# BMS_Bottom_Segment.net
KiCad netlist of a schematic drawn in EAGLE
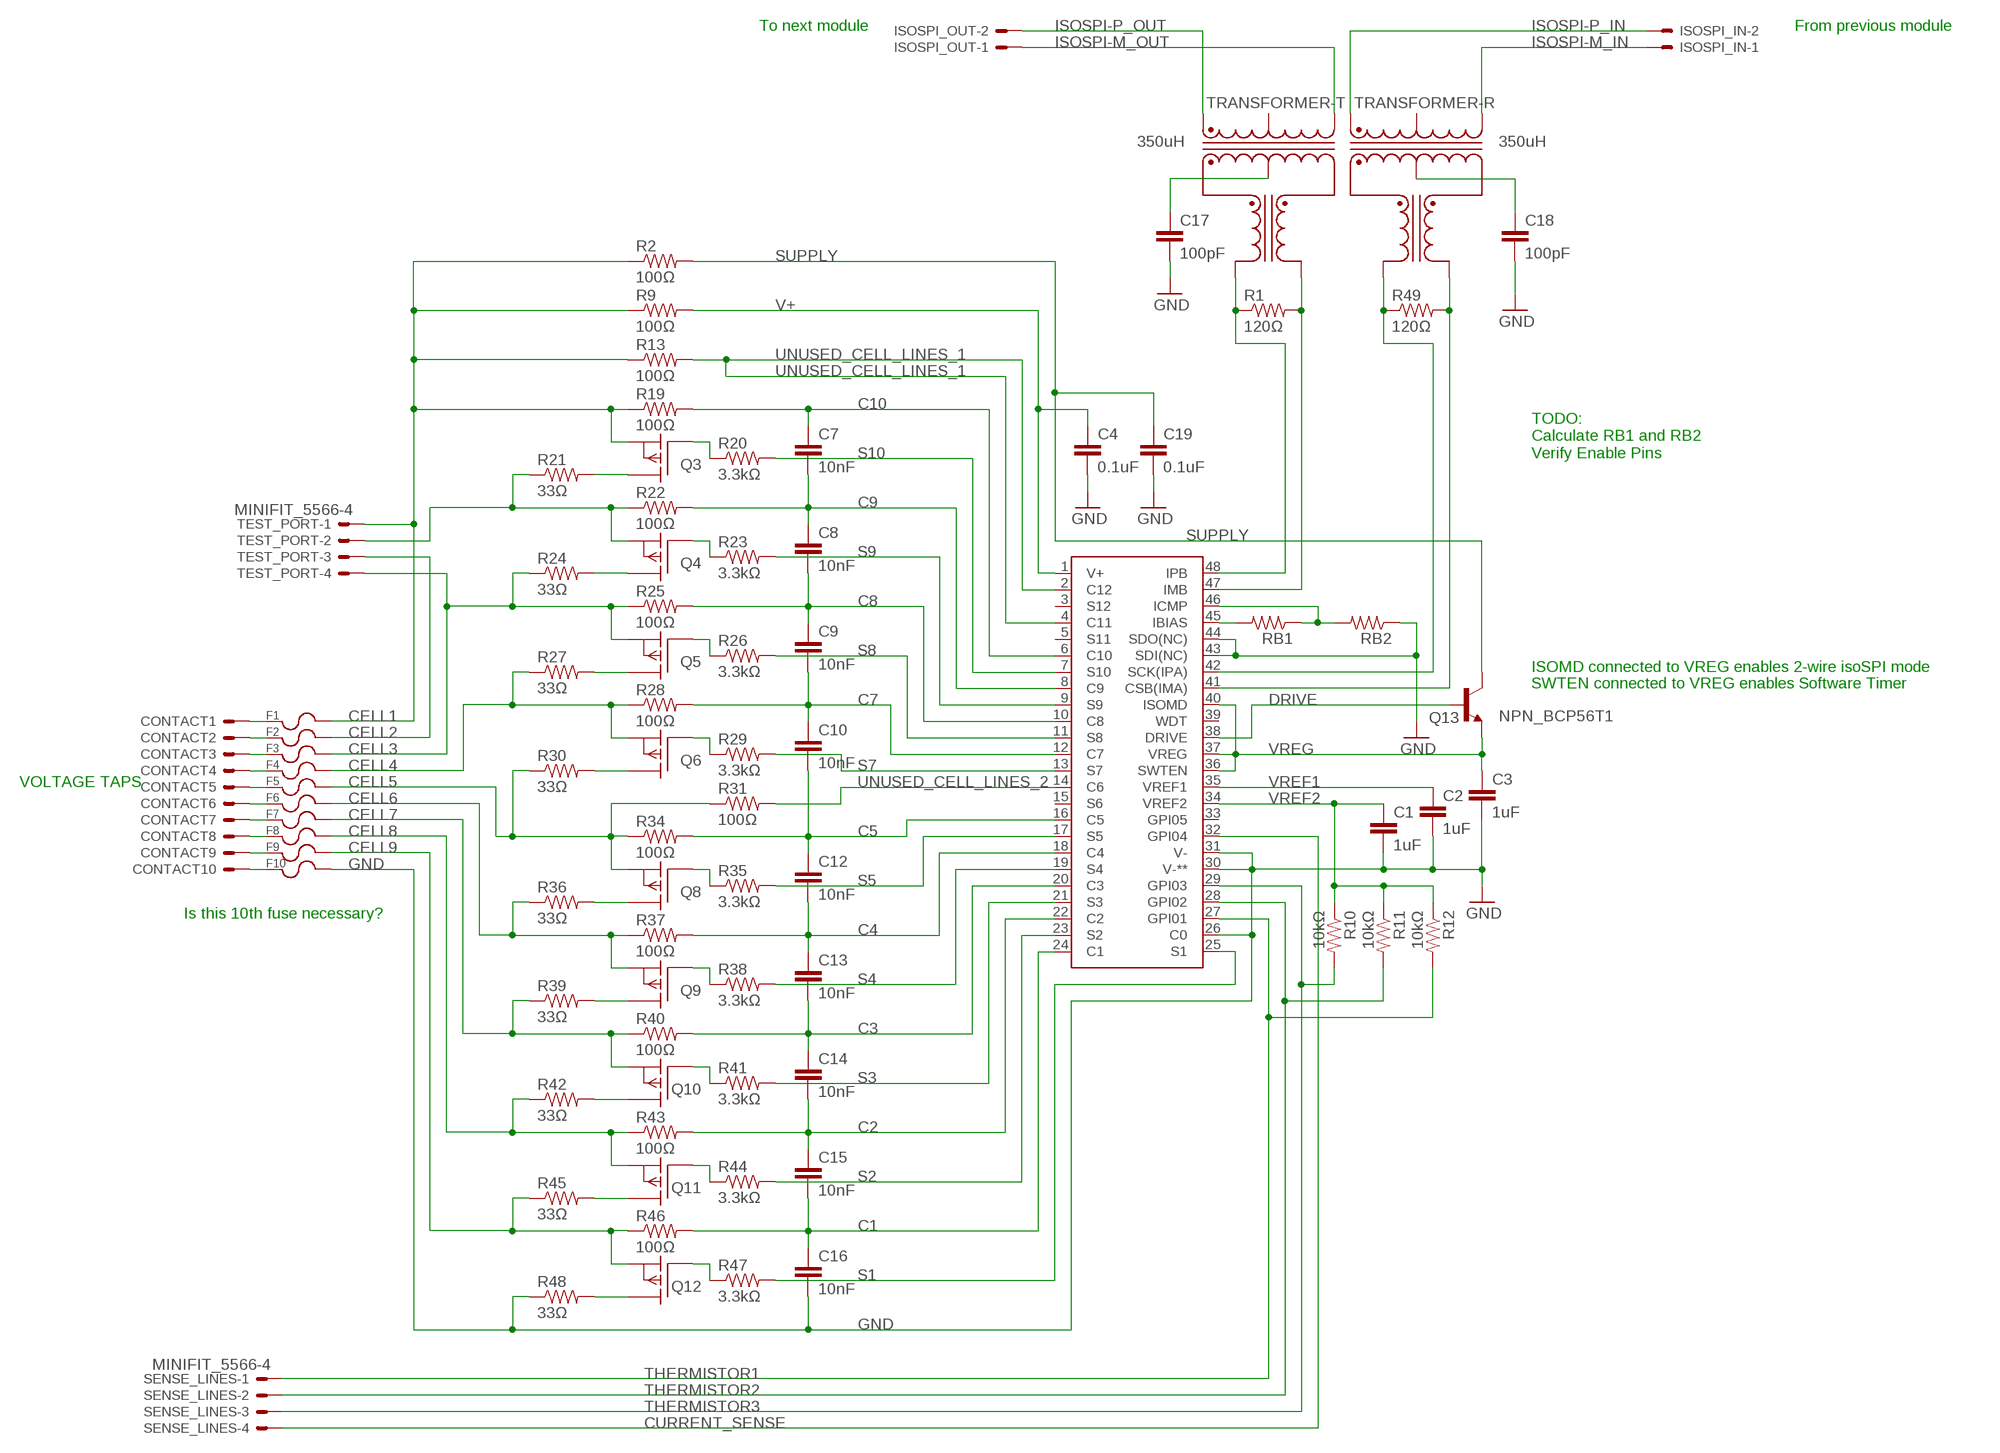
[diagram p0: schematic, sheet 1]

(export (version "E")
  (design (tool "Eeschema 10.0.6"))
  (components
    (comp (ref "C1")
      (value "1uF")
      (footprint "eagle-import:0805")
      (libsource (lib "eagle-import") (part "CAP0805"))
    )
    (comp (ref "C2")
      (value "1uF")
      (footprint "eagle-import:0805")
      (libsource (lib "eagle-import") (part "CAP0805"))
    )
    (comp (ref "C3")
      (value "1uF")
      (footprint "eagle-import:0805")
      (libsource (lib "eagle-import") (part "CAP0805"))
    )
    (comp (ref "C4")
      (value "0.1uF")
      (footprint "eagle-import:0805")
      (libsource (lib "eagle-import") (part "CAP0805"))
    )
    (comp (ref "C7")
      (value "10nF")
      (footprint "eagle-import:0805")
      (libsource (lib "eagle-import") (part "CAP0805"))
    )
    (comp (ref "C8")
      (value "10nF")
      (footprint "eagle-import:0805")
      (libsource (lib "eagle-import") (part "CAP0805"))
    )
    (comp (ref "C9")
      (value "10nF")
      (footprint "eagle-import:0805")
      (libsource (lib "eagle-import") (part "CAP0805"))
    )
    (comp (ref "C10")
      (value "10nF")
      (footprint "eagle-import:0805")
      (libsource (lib "eagle-import") (part "CAP0805"))
    )
    (comp (ref "C12")
      (value "10nF")
      (footprint "eagle-import:0805")
      (libsource (lib "eagle-import") (part "CAP0805"))
    )
    (comp (ref "C13")
      (value "10nF")
      (footprint "eagle-import:0805")
      (libsource (lib "eagle-import") (part "CAP0805"))
    )
    (comp (ref "C14")
      (value "10nF")
      (footprint "eagle-import:0805")
      (libsource (lib "eagle-import") (part "CAP0805"))
    )
    (comp (ref "C15")
      (value "10nF")
      (footprint "eagle-import:0805")
      (libsource (lib "eagle-import") (part "CAP0805"))
    )
    (comp (ref "C16")
      (value "10nF")
      (footprint "eagle-import:0805")
      (libsource (lib "eagle-import") (part "CAP0805"))
    )
    (comp (ref "C17")
      (value "100pF")
      (footprint "eagle-import:0805")
      (libsource (lib "eagle-import") (part "CAP0805"))
    )
    (comp (ref "C18")
      (value "100pF")
      (footprint "eagle-import:0805")
      (libsource (lib "eagle-import") (part "CAP0805"))
    )
    (comp (ref "C19")
      (value "0.1uF")
      (footprint "eagle-import:0805")
      (libsource (lib "eagle-import") (part "CAP0805"))
    )
    (comp (ref "CONTACT1")
      (value "SPRING_CONTACT")
      (footprint "eagle-import:S1791-42R")
      (libsource (lib "eagle-import") (part "SPRING_CONTACT"))
    )
    (comp (ref "CONTACT2")
      (value "SPRING_CONTACT")
      (footprint "eagle-import:S1791-42R")
      (libsource (lib "eagle-import") (part "SPRING_CONTACT"))
    )
    (comp (ref "CONTACT3")
      (value "SPRING_CONTACT")
      (footprint "eagle-import:S1791-42R")
      (libsource (lib "eagle-import") (part "SPRING_CONTACT"))
    )
    (comp (ref "CONTACT4")
      (value "SPRING_CONTACT")
      (footprint "eagle-import:S1791-42R")
      (libsource (lib "eagle-import") (part "SPRING_CONTACT"))
    )
    (comp (ref "CONTACT5")
      (value "SPRING_CONTACT")
      (footprint "eagle-import:S1791-42R")
      (libsource (lib "eagle-import") (part "SPRING_CONTACT"))
    )
    (comp (ref "CONTACT6")
      (value "SPRING_CONTACT")
      (footprint "eagle-import:S1791-42R")
      (libsource (lib "eagle-import") (part "SPRING_CONTACT"))
    )
    (comp (ref "CONTACT7")
      (value "SPRING_CONTACT")
      (footprint "eagle-import:S1791-42R")
      (libsource (lib "eagle-import") (part "SPRING_CONTACT"))
    )
    (comp (ref "CONTACT8")
      (value "SPRING_CONTACT")
      (footprint "eagle-import:S1791-42R")
      (libsource (lib "eagle-import") (part "SPRING_CONTACT"))
    )
    (comp (ref "CONTACT9")
      (value "SPRING_CONTACT")
      (footprint "eagle-import:S1791-42R")
      (libsource (lib "eagle-import") (part "SPRING_CONTACT"))
    )
    (comp (ref "CONTACT10")
      (value "SPRING_CONTACT")
      (footprint "eagle-import:S1791-42R")
      (libsource (lib "eagle-import") (part "SPRING_CONTACT"))
    )
    (comp (ref "F1")
      (value "0751.0110_FUSE_CLIP")
      (footprint "eagle-import:0751.0110")
      (libsource (lib "eagle-import") (part "0751.0110_FUSE_CLIP"))
    )
    (comp (ref "F2")
      (value "0751.0110_FUSE_CLIP")
      (footprint "eagle-import:0751.0110")
      (libsource (lib "eagle-import") (part "0751.0110_FUSE_CLIP"))
    )
    (comp (ref "F3")
      (value "0751.0110_FUSE_CLIP")
      (footprint "eagle-import:0751.0110")
      (libsource (lib "eagle-import") (part "0751.0110_FUSE_CLIP"))
    )
    (comp (ref "F4")
      (value "0751.0110_FUSE_CLIP")
      (footprint "eagle-import:0751.0110")
      (libsource (lib "eagle-import") (part "0751.0110_FUSE_CLIP"))
    )
    (comp (ref "F5")
      (value "0751.0110_FUSE_CLIP")
      (footprint "eagle-import:0751.0110")
      (libsource (lib "eagle-import") (part "0751.0110_FUSE_CLIP"))
    )
    (comp (ref "F6")
      (value "0751.0110_FUSE_CLIP")
      (footprint "eagle-import:0751.0110")
      (libsource (lib "eagle-import") (part "0751.0110_FUSE_CLIP"))
    )
    (comp (ref "F7")
      (value "0751.0110_FUSE_CLIP")
      (footprint "eagle-import:0751.0110")
      (libsource (lib "eagle-import") (part "0751.0110_FUSE_CLIP"))
    )
    (comp (ref "F8")
      (value "0751.0110_FUSE_CLIP")
      (footprint "eagle-import:0751.0110")
      (libsource (lib "eagle-import") (part "0751.0110_FUSE_CLIP"))
    )
    (comp (ref "F9")
      (value "0751.0110_FUSE_CLIP")
      (footprint "eagle-import:0751.0110")
      (libsource (lib "eagle-import") (part "0751.0110_FUSE_CLIP"))
    )
    (comp (ref "F10")
      (value "0751.0110_FUSE_CLIP")
      (footprint "eagle-import:0751.0110")
      (libsource (lib "eagle-import") (part "0751.0110_FUSE_CLIP"))
    )
    (comp (ref "ISOSPI_IN")
      (value "MINIFIT_5566-2")
      (footprint "eagle-import:MINIFIT_5566-2")
      (libsource (lib "eagle-import") (part "MINIFIT_5566-2"))
    )
    (comp (ref "ISOSPI_OUT")
      (value "MINIFIT_5566-2")
      (footprint "eagle-import:MINIFIT_5566-2")
      (libsource (lib "eagle-import") (part "MINIFIT_5566-2"))
    )
    (comp (ref "Q3")
      (value "P-CHANNEL_MOSFET_DMP3099L-7")
      (footprint "eagle-import:SOT23")
      (libsource (lib "eagle-import") (part "P-CHANNEL_MOSFET_DMP3099L-7"))
    )
    (comp (ref "Q4")
      (value "P-CHANNEL_MOSFET_DMP3099L-7")
      (footprint "eagle-import:SOT23")
      (libsource (lib "eagle-import") (part "P-CHANNEL_MOSFET_DMP3099L-7"))
    )
    (comp (ref "Q5")
      (value "P-CHANNEL_MOSFET_DMP3099L-7")
      (footprint "eagle-import:SOT23")
      (libsource (lib "eagle-import") (part "P-CHANNEL_MOSFET_DMP3099L-7"))
    )
    (comp (ref "Q6")
      (value "P-CHANNEL_MOSFET_DMP3099L-7")
      (footprint "eagle-import:SOT23")
      (libsource (lib "eagle-import") (part "P-CHANNEL_MOSFET_DMP3099L-7"))
    )
    (comp (ref "Q8")
      (value "P-CHANNEL_MOSFET_DMP3099L-7")
      (footprint "eagle-import:SOT23")
      (libsource (lib "eagle-import") (part "P-CHANNEL_MOSFET_DMP3099L-7"))
    )
    (comp (ref "Q9")
      (value "P-CHANNEL_MOSFET_DMP3099L-7")
      (footprint "eagle-import:SOT23")
      (libsource (lib "eagle-import") (part "P-CHANNEL_MOSFET_DMP3099L-7"))
    )
    (comp (ref "Q10")
      (value "P-CHANNEL_MOSFET_DMP3099L-7")
      (footprint "eagle-import:SOT23")
      (libsource (lib "eagle-import") (part "P-CHANNEL_MOSFET_DMP3099L-7"))
    )
    (comp (ref "Q11")
      (value "P-CHANNEL_MOSFET_DMP3099L-7")
      (footprint "eagle-import:SOT23")
      (libsource (lib "eagle-import") (part "P-CHANNEL_MOSFET_DMP3099L-7"))
    )
    (comp (ref "Q12")
      (value "P-CHANNEL_MOSFET_DMP3099L-7")
      (footprint "eagle-import:SOT23")
      (libsource (lib "eagle-import") (part "P-CHANNEL_MOSFET_DMP3099L-7"))
    )
    (comp (ref "Q13")
      (value "NPN_BCP56T1")
      (footprint "eagle-import:SOT223")
      (libsource (lib "eagle-import") (part "NPN_BCP56T1"))
    )
    (comp (ref "R1")
      (value "120Ω")
      (footprint "eagle-import:0805")
      (libsource (lib "eagle-import") (part "RESISTOR0805-RES"))
    )
    (comp (ref "R2")
      (value "100Ω")
      (footprint "eagle-import:0805")
      (libsource (lib "eagle-import") (part "RESISTOR0805-RES"))
    )
    (comp (ref "R9")
      (value "100Ω")
      (footprint "eagle-import:0805")
      (libsource (lib "eagle-import") (part "RESISTOR0805-RES"))
    )
    (comp (ref "R10")
      (value "10kΩ")
      (footprint "eagle-import:0805")
      (libsource (lib "eagle-import") (part "RESISTOR0805-RES"))
    )
    (comp (ref "R11")
      (value "10kΩ")
      (footprint "eagle-import:0805")
      (libsource (lib "eagle-import") (part "RESISTOR0805-RES"))
    )
    (comp (ref "R12")
      (value "10kΩ")
      (footprint "eagle-import:0805")
      (libsource (lib "eagle-import") (part "RESISTOR0805-RES"))
    )
    (comp (ref "R13")
      (value "100Ω")
      (footprint "eagle-import:0805")
      (libsource (lib "eagle-import") (part "RESISTOR0805-RES"))
    )
    (comp (ref "R19")
      (value "100Ω")
      (footprint "eagle-import:0805")
      (libsource (lib "eagle-import") (part "RESISTOR0805-RES"))
    )
    (comp (ref "R20")
      (value "3.3kΩ")
      (footprint "eagle-import:0805")
      (libsource (lib "eagle-import") (part "RESISTOR0805-RES"))
    )
    (comp (ref "R21")
      (value "33Ω")
      (footprint "eagle-import:R2512")
      (libsource (lib "eagle-import") (part "RESISTOR2512"))
    )
    (comp (ref "R22")
      (value "100Ω")
      (footprint "eagle-import:0805")
      (libsource (lib "eagle-import") (part "RESISTOR0805-RES"))
    )
    (comp (ref "R23")
      (value "3.3kΩ")
      (footprint "eagle-import:0805")
      (libsource (lib "eagle-import") (part "RESISTOR0805-RES"))
    )
    (comp (ref "R24")
      (value "33Ω")
      (footprint "eagle-import:R2512")
      (libsource (lib "eagle-import") (part "RESISTOR2512"))
    )
    (comp (ref "R25")
      (value "100Ω")
      (footprint "eagle-import:0805")
      (libsource (lib "eagle-import") (part "RESISTOR0805-RES"))
    )
    (comp (ref "R26")
      (value "3.3kΩ")
      (footprint "eagle-import:0805")
      (libsource (lib "eagle-import") (part "RESISTOR0805-RES"))
    )
    (comp (ref "R27")
      (value "33Ω")
      (footprint "eagle-import:R2512")
      (libsource (lib "eagle-import") (part "RESISTOR2512"))
    )
    (comp (ref "R28")
      (value "100Ω")
      (footprint "eagle-import:0805")
      (libsource (lib "eagle-import") (part "RESISTOR0805-RES"))
    )
    (comp (ref "R29")
      (value "3.3kΩ")
      (footprint "eagle-import:0805")
      (libsource (lib "eagle-import") (part "RESISTOR0805-RES"))
    )
    (comp (ref "R30")
      (value "33Ω")
      (footprint "eagle-import:R2512")
      (libsource (lib "eagle-import") (part "RESISTOR2512"))
    )
    (comp (ref "R31")
      (value "100Ω")
      (footprint "eagle-import:0805")
      (libsource (lib "eagle-import") (part "RESISTOR0805-RES"))
    )
    (comp (ref "R34")
      (value "100Ω")
      (footprint "eagle-import:0805")
      (libsource (lib "eagle-import") (part "RESISTOR0805-RES"))
    )
    (comp (ref "R35")
      (value "3.3kΩ")
      (footprint "eagle-import:0805")
      (libsource (lib "eagle-import") (part "RESISTOR0805-RES"))
    )
    (comp (ref "R36")
      (value "33Ω")
      (footprint "eagle-import:R2512")
      (libsource (lib "eagle-import") (part "RESISTOR2512"))
    )
    (comp (ref "R37")
      (value "100Ω")
      (footprint "eagle-import:0805")
      (libsource (lib "eagle-import") (part "RESISTOR0805-RES"))
    )
    (comp (ref "R38")
      (value "3.3kΩ")
      (footprint "eagle-import:0805")
      (libsource (lib "eagle-import") (part "RESISTOR0805-RES"))
    )
    (comp (ref "R39")
      (value "33Ω")
      (footprint "eagle-import:R2512")
      (libsource (lib "eagle-import") (part "RESISTOR2512"))
    )
    (comp (ref "R40")
      (value "100Ω")
      (footprint "eagle-import:0805")
      (libsource (lib "eagle-import") (part "RESISTOR0805-RES"))
    )
    (comp (ref "R41")
      (value "3.3kΩ")
      (footprint "eagle-import:0805")
      (libsource (lib "eagle-import") (part "RESISTOR0805-RES"))
    )
    (comp (ref "R42")
      (value "33Ω")
      (footprint "eagle-import:R2512")
      (libsource (lib "eagle-import") (part "RESISTOR2512"))
    )
    (comp (ref "R43")
      (value "100Ω")
      (footprint "eagle-import:0805")
      (libsource (lib "eagle-import") (part "RESISTOR0805-RES"))
    )
    (comp (ref "R44")
      (value "3.3kΩ")
      (footprint "eagle-import:0805")
      (libsource (lib "eagle-import") (part "RESISTOR0805-RES"))
    )
    (comp (ref "R45")
      (value "33Ω")
      (footprint "eagle-import:R2512")
      (libsource (lib "eagle-import") (part "RESISTOR2512"))
    )
    (comp (ref "R46")
      (value "100Ω")
      (footprint "eagle-import:0805")
      (libsource (lib "eagle-import") (part "RESISTOR0805-RES"))
    )
    (comp (ref "R47")
      (value "3.3kΩ")
      (footprint "eagle-import:0805")
      (libsource (lib "eagle-import") (part "RESISTOR0805-RES"))
    )
    (comp (ref "R48")
      (value "33Ω")
      (footprint "eagle-import:R2512")
      (libsource (lib "eagle-import") (part "RESISTOR2512"))
    )
    (comp (ref "R49")
      (value "120Ω")
      (footprint "eagle-import:0805")
      (libsource (lib "eagle-import") (part "RESISTOR0805-RES"))
    )
    (comp (ref "RB1")
      (value "RESISTOR0805-RES")
      (footprint "eagle-import:0805")
      (libsource (lib "eagle-import") (part "RESISTOR0805-RES"))
    )
    (comp (ref "RB2")
      (value "RESISTOR0805-RES")
      (footprint "eagle-import:0805")
      (libsource (lib "eagle-import") (part "RESISTOR0805-RES"))
    )
    (comp (ref "SENSE_LINES")
      (value "MINIFIT_5566-4")
      (footprint "eagle-import:MINIFIT_5566-4")
      (libsource (lib "eagle-import") (part "MINIFIT_5566-4"))
    )
    (comp (ref "TEST_PORT")
      (value "MINIFIT_5566-4")
      (footprint "eagle-import:MINIFIT_5566-4")
      (libsource (lib "eagle-import") (part "MINIFIT_5566-4"))
    )
    (comp (ref "TRANSFORMER-")
      (value "350uH")
      (footprint "eagle-import:749010013")
      (libsource (lib "eagle-import") (part "TRANSFORMER_749010013"))
    )
    (comp (ref "U$2")
      (value "LTC6804-1")
      (footprint "eagle-import:LTC6804")
      (libsource (lib "eagle-import") (part "LTC6804-1"))
    )
  )
  (nets
    (net (code "1") (name "/C1") (class "Default")
      (node (ref "C15") (pin "2") (pinfunction "2_2") (pintype "passive"))
      (node (ref "C16") (pin "1") (pinfunction "1_1") (pintype "passive"))
      (node (ref "R46") (pin "2") (pinfunction "2_2") (pintype "passive"))
      (node (ref "U$2") (pin "24") (pinfunction "C1_24") (pintype "bidirectional"))
    )
    (net (code "2") (name "/C2") (class "Default")
      (node (ref "C14") (pin "2") (pinfunction "2_2") (pintype "passive"))
      (node (ref "C15") (pin "1") (pinfunction "1_1") (pintype "passive"))
      (node (ref "R43") (pin "2") (pinfunction "2_2") (pintype "passive"))
      (node (ref "U$2") (pin "22") (pinfunction "C2_22") (pintype "bidirectional"))
    )
    (net (code "3") (name "/C3") (class "Default")
      (node (ref "C13") (pin "2") (pinfunction "2_2") (pintype "passive"))
      (node (ref "C14") (pin "1") (pinfunction "1_1") (pintype "passive"))
      (node (ref "R40") (pin "2") (pinfunction "2_2") (pintype "passive"))
      (node (ref "U$2") (pin "20") (pinfunction "C3_20") (pintype "bidirectional"))
    )
    (net (code "4") (name "/C4") (class "Default")
      (node (ref "C12") (pin "2") (pinfunction "2_2") (pintype "passive"))
      (node (ref "C13") (pin "1") (pinfunction "1_1") (pintype "passive"))
      (node (ref "R37") (pin "2") (pinfunction "2_2") (pintype "passive"))
      (node (ref "U$2") (pin "18") (pinfunction "C4_18") (pintype "bidirectional"))
    )
    (net (code "5") (name "/C5") (class "Default")
      (node (ref "C10") (pin "2") (pinfunction "2_2") (pintype "passive"))
      (node (ref "C12") (pin "1") (pinfunction "1_1") (pintype "passive"))
      (node (ref "R34") (pin "2") (pinfunction "2_2") (pintype "passive"))
      (node (ref "U$2") (pin "16") (pinfunction "C5_16") (pintype "bidirectional"))
    )
    (net (code "6") (name "/C7") (class "Default")
      (node (ref "C10") (pin "1") (pinfunction "1_1") (pintype "passive"))
      (node (ref "C9") (pin "2") (pinfunction "2_2") (pintype "passive"))
      (node (ref "R28") (pin "2") (pinfunction "2_2") (pintype "passive"))
      (node (ref "U$2") (pin "12") (pinfunction "C7_12") (pintype "bidirectional"))
    )
    (net (code "7") (name "/C8") (class "Default")
      (node (ref "C8") (pin "2") (pinfunction "2_2") (pintype "passive"))
      (node (ref "C9") (pin "1") (pinfunction "1_1") (pintype "passive"))
      (node (ref "R25") (pin "2") (pinfunction "2_2") (pintype "passive"))
      (node (ref "U$2") (pin "10") (pinfunction "C8_10") (pintype "bidirectional"))
    )
    (net (code "8") (name "/C9") (class "Default")
      (node (ref "C7") (pin "2") (pinfunction "2_2") (pintype "passive"))
      (node (ref "C8") (pin "1") (pinfunction "1_1") (pintype "passive"))
      (node (ref "R22") (pin "2") (pinfunction "2_2") (pintype "passive"))
      (node (ref "U$2") (pin "8") (pinfunction "C9_8") (pintype "bidirectional"))
    )
    (net (code "9") (name "/C10") (class "Default")
      (node (ref "C7") (pin "1") (pinfunction "1_1") (pintype "passive"))
      (node (ref "R19") (pin "2") (pinfunction "2_2") (pintype "passive"))
      (node (ref "U$2") (pin "6") (pinfunction "C10_6") (pintype "bidirectional"))
    )
    (net (code "10") (name "/CELL1") (class "Default")
      (node (ref "F1") (pin "R1") (pinfunction "2_R1") (pintype "bidirectional"))
      (node (ref "F1") (pin "R2") (pinfunction "2_R2") (pintype "bidirectional"))
      (node (ref "Q3") (pin "2") (pinfunction "S_2") (pintype "passive"))
      (node (ref "R13") (pin "1") (pinfunction "1_1") (pintype "passive"))
      (node (ref "R19") (pin "1") (pinfunction "1_1") (pintype "passive"))
      (node (ref "R2") (pin "1") (pinfunction "1_1") (pintype "passive"))
      (node (ref "R9") (pin "1") (pinfunction "1_1") (pintype "passive"))
      (node (ref "TEST_PORT") (pin "1") (pinfunction "S_1") (pintype "passive"))
    )
    (net (code "11") (name "/CELL2") (class "Default")
      (node (ref "F2") (pin "R1") (pinfunction "2_R1") (pintype "bidirectional"))
      (node (ref "F2") (pin "R2") (pinfunction "2_R2") (pintype "bidirectional"))
      (node (ref "Q4") (pin "2") (pinfunction "S_2") (pintype "passive"))
      (node (ref "R21") (pin "1") (pinfunction "1_1") (pintype "passive"))
      (node (ref "R22") (pin "1") (pinfunction "1_1") (pintype "passive"))
      (node (ref "TEST_PORT") (pin "2") (pinfunction "S_2") (pintype "passive"))
      (node (ref "TEST_PORT") (pin "3") (pinfunction "S_3") (pintype "passive"))
    )
    (net (code "12") (name "/CELL3") (class "Default")
      (node (ref "F3") (pin "R1") (pinfunction "2_R1") (pintype "bidirectional"))
      (node (ref "F3") (pin "R2") (pinfunction "2_R2") (pintype "bidirectional"))
      (node (ref "Q5") (pin "2") (pinfunction "S_2") (pintype "passive"))
      (node (ref "R24") (pin "1") (pinfunction "1_1") (pintype "passive"))
      (node (ref "R25") (pin "1") (pinfunction "1_1") (pintype "passive"))
      (node (ref "TEST_PORT") (pin "4") (pinfunction "S_4") (pintype "passive"))
    )
    (net (code "13") (name "/CELL4") (class "Default")
      (node (ref "F4") (pin "R1") (pinfunction "2_R1") (pintype "bidirectional"))
      (node (ref "F4") (pin "R2") (pinfunction "2_R2") (pintype "bidirectional"))
      (node (ref "Q6") (pin "2") (pinfunction "S_2") (pintype "passive"))
      (node (ref "R27") (pin "1") (pinfunction "1_1") (pintype "passive"))
      (node (ref "R28") (pin "1") (pinfunction "1_1") (pintype "passive"))
    )
    (net (code "14") (name "/CELL5") (class "Default")
      (node (ref "F5") (pin "R1") (pinfunction "2_R1") (pintype "bidirectional"))
      (node (ref "F5") (pin "R2") (pinfunction "2_R2") (pintype "bidirectional"))
      (node (ref "Q8") (pin "2") (pinfunction "S_2") (pintype "passive"))
      (node (ref "R30") (pin "1") (pinfunction "1_1") (pintype "passive"))
      (node (ref "R31") (pin "1") (pinfunction "1_1") (pintype "passive"))
      (node (ref "R34") (pin "1") (pinfunction "1_1") (pintype "passive"))
    )
    (net (code "15") (name "/CELL6") (class "Default")
      (node (ref "F6") (pin "R1") (pinfunction "2_R1") (pintype "bidirectional"))
      (node (ref "F6") (pin "R2") (pinfunction "2_R2") (pintype "bidirectional"))
      (node (ref "Q9") (pin "2") (pinfunction "S_2") (pintype "passive"))
      (node (ref "R36") (pin "1") (pinfunction "1_1") (pintype "passive"))
      (node (ref "R37") (pin "1") (pinfunction "1_1") (pintype "passive"))
    )
    (net (code "16") (name "/CELL7") (class "Default")
      (node (ref "F7") (pin "R1") (pinfunction "2_R1") (pintype "bidirectional"))
      (node (ref "F7") (pin "R2") (pinfunction "2_R2") (pintype "bidirectional"))
      (node (ref "Q10") (pin "2") (pinfunction "S_2") (pintype "passive"))
      (node (ref "R39") (pin "1") (pinfunction "1_1") (pintype "passive"))
      (node (ref "R40") (pin "1") (pinfunction "1_1") (pintype "passive"))
    )
    (net (code "17") (name "/CELL8") (class "Default")
      (node (ref "F8") (pin "R1") (pinfunction "2_R1") (pintype "bidirectional"))
      (node (ref "F8") (pin "R2") (pinfunction "2_R2") (pintype "bidirectional"))
      (node (ref "Q11") (pin "2") (pinfunction "S_2") (pintype "passive"))
      (node (ref "R42") (pin "1") (pinfunction "1_1") (pintype "passive"))
      (node (ref "R43") (pin "1") (pinfunction "1_1") (pintype "passive"))
    )
    (net (code "18") (name "/CELL9") (class "Default")
      (node (ref "F9") (pin "R1") (pinfunction "2_R1") (pintype "bidirectional"))
      (node (ref "F9") (pin "R2") (pinfunction "2_R2") (pintype "bidirectional"))
      (node (ref "Q12") (pin "2") (pinfunction "S_2") (pintype "passive"))
      (node (ref "R45") (pin "1") (pinfunction "1_1") (pintype "passive"))
      (node (ref "R46") (pin "1") (pinfunction "1_1") (pintype "passive"))
    )
    (net (code "19") (name "/CURRENT_SENSE") (class "Default")
      (node (ref "SENSE_LINES") (pin "4") (pinfunction "S_4") (pintype "passive"))
      (node (ref "U$2") (pin "32") (pinfunction "GPI04_32") (pintype "bidirectional"))
    )
    (net (code "20") (name "/DRIVE") (class "Default")
      (node (ref "Q13") (pin "1") (pinfunction "BASE_1") (pintype "passive"))
      (node (ref "U$2") (pin "38") (pinfunction "DRIVE_38") (pintype "bidirectional"))
    )
    (net (code "21") (name "/ISOSPI-M_IN") (class "Default")
      (node (ref "ISOSPI_IN") (pin "1") (pinfunction "S_1") (pintype "passive"))
      (node (ref "TRANSFORMER-") (pin "8") (pinfunction "D-_8") (pintype "passive"))
    )
    (net (code "22") (name "/ISOSPI-M_OUT") (class "Default")
      (node (ref "ISOSPI_OUT") (pin "1") (pinfunction "S_1") (pintype "passive"))
      (node (ref "TRANSFORMER-") (pin "3") (pinfunction "D-_3") (pintype "passive"))
    )
    (net (code "23") (name "/ISOSPI-P_IN") (class "Default")
      (node (ref "ISOSPI_IN") (pin "2") (pinfunction "S_2") (pintype "passive"))
      (node (ref "TRANSFORMER-") (pin "6") (pinfunction "D+_6") (pintype "passive"))
    )
    (net (code "24") (name "/ISOSPI-P_OUT") (class "Default")
      (node (ref "ISOSPI_OUT") (pin "2") (pinfunction "S_2") (pintype "passive"))
      (node (ref "TRANSFORMER-") (pin "1") (pinfunction "D+_1") (pintype "passive"))
    )
    (net (code "25") (name "/S1") (class "Default")
      (node (ref "R47") (pin "2") (pinfunction "2_2") (pintype "passive"))
      (node (ref "U$2") (pin "25") (pinfunction "S1_25") (pintype "bidirectional"))
    )
    (net (code "26") (name "/S2") (class "Default")
      (node (ref "R44") (pin "2") (pinfunction "2_2") (pintype "passive"))
      (node (ref "U$2") (pin "23") (pinfunction "S2_23") (pintype "bidirectional"))
    )
    (net (code "27") (name "/S3") (class "Default")
      (node (ref "R41") (pin "2") (pinfunction "2_2") (pintype "passive"))
      (node (ref "U$2") (pin "21") (pinfunction "S3_21") (pintype "bidirectional"))
    )
    (net (code "28") (name "/S4") (class "Default")
      (node (ref "R38") (pin "2") (pinfunction "2_2") (pintype "passive"))
      (node (ref "U$2") (pin "19") (pinfunction "S4_19") (pintype "bidirectional"))
    )
    (net (code "29") (name "/S5") (class "Default")
      (node (ref "R35") (pin "2") (pinfunction "2_2") (pintype "passive"))
      (node (ref "U$2") (pin "17") (pinfunction "S5_17") (pintype "bidirectional"))
    )
    (net (code "30") (name "/S7") (class "Default")
      (node (ref "R29") (pin "2") (pinfunction "2_2") (pintype "passive"))
      (node (ref "U$2") (pin "13") (pinfunction "S7_13") (pintype "bidirectional"))
    )
    (net (code "31") (name "/S8") (class "Default")
      (node (ref "R26") (pin "2") (pinfunction "2_2") (pintype "passive"))
      (node (ref "U$2") (pin "11") (pinfunction "S8_11") (pintype "bidirectional"))
    )
    (net (code "32") (name "/S9") (class "Default")
      (node (ref "R23") (pin "2") (pinfunction "2_2") (pintype "passive"))
      (node (ref "U$2") (pin "9") (pinfunction "S9_9") (pintype "bidirectional"))
    )
    (net (code "33") (name "/S10") (class "Default")
      (node (ref "R20") (pin "2") (pinfunction "2_2") (pintype "passive"))
      (node (ref "U$2") (pin "7") (pinfunction "S10_7") (pintype "bidirectional"))
    )
    (net (code "34") (name "/SUPPLY") (class "Default")
      (node (ref "C19") (pin "1") (pinfunction "1_1") (pintype "passive"))
      (node (ref "Q13") (pin "2") (pinfunction "COLLECTOR_2") (pintype "passive"))
      (node (ref "Q13") (pin "4") (pinfunction "COLLECTOR_4") (pintype "passive"))
      (node (ref "R2") (pin "2") (pinfunction "2_2") (pintype "passive"))
    )
    (net (code "35") (name "/THERMISTOR1") (class "Default")
      (node (ref "R12") (pin "2") (pinfunction "2_2") (pintype "passive"))
      (node (ref "SENSE_LINES") (pin "1") (pinfunction "S_1") (pintype "passive"))
      (node (ref "U$2") (pin "27") (pinfunction "GPI01_27") (pintype "bidirectional"))
    )
    (net (code "36") (name "/THERMISTOR2") (class "Default")
      (node (ref "R11") (pin "2") (pinfunction "2_2") (pintype "passive"))
      (node (ref "SENSE_LINES") (pin "2") (pinfunction "S_2") (pintype "passive"))
      (node (ref "U$2") (pin "28") (pinfunction "GPI02_28") (pintype "bidirectional"))
    )
    (net (code "37") (name "/THERMISTOR3") (class "Default")
      (node (ref "R10") (pin "2") (pinfunction "2_2") (pintype "passive"))
      (node (ref "SENSE_LINES") (pin "3") (pinfunction "S_3") (pintype "passive"))
      (node (ref "U$2") (pin "29") (pinfunction "GPI03_29") (pintype "bidirectional"))
    )
    (net (code "38") (name "/UNUSED_CELL_LINES_1") (class "Default")
      (node (ref "R13") (pin "2") (pinfunction "2_2") (pintype "passive"))
      (node (ref "U$2") (pin "2") (pinfunction "C12_2") (pintype "bidirectional"))
      (node (ref "U$2") (pin "4") (pinfunction "C11_4") (pintype "bidirectional"))
    )
    (net (code "39") (name "/UNUSED_CELL_LINES_2") (class "Default")
      (node (ref "R31") (pin "2") (pinfunction "2_2") (pintype "passive"))
      (node (ref "U$2") (pin "14") (pinfunction "C6_14") (pintype "bidirectional"))
    )
    (net (code "40") (name "/V+") (class "Default")
      (node (ref "C4") (pin "1") (pinfunction "1_1") (pintype "passive"))
      (node (ref "R9") (pin "2") (pinfunction "2_2") (pintype "passive"))
      (node (ref "U$2") (pin "1") (pinfunction "V+_1") (pintype "bidirectional"))
    )
    (net (code "41") (name "/VREF1") (class "Default")
      (node (ref "C2") (pin "1") (pinfunction "1_1") (pintype "passive"))
      (node (ref "U$2") (pin "35") (pinfunction "VREF1_35") (pintype "bidirectional"))
    )
    (net (code "42") (name "/VREF2") (class "Default")
      (node (ref "C1") (pin "1") (pinfunction "1_1") (pintype "passive"))
      (node (ref "R10") (pin "1") (pinfunction "1_1") (pintype "passive"))
      (node (ref "R11") (pin "1") (pinfunction "1_1") (pintype "passive"))
      (node (ref "R12") (pin "1") (pinfunction "1_1") (pintype "passive"))
      (node (ref "U$2") (pin "34") (pinfunction "VREF2_34") (pintype "bidirectional"))
    )
    (net (code "43") (name "/VREG") (class "Default")
      (node (ref "C3") (pin "1") (pinfunction "1_1") (pintype "passive"))
      (node (ref "Q13") (pin "3") (pinfunction "EMITTER_3") (pintype "passive"))
      (node (ref "U$2") (pin "36") (pinfunction "SWTEN_36") (pintype "bidirectional"))
      (node (ref "U$2") (pin "37") (pinfunction "VREG_37") (pintype "bidirectional"))
      (node (ref "U$2") (pin "40") (pinfunction "ISOMD_40") (pintype "bidirectional"))
    )
    (net (code "44") (name "GND") (class "Default")
      (node (ref "C1") (pin "2") (pinfunction "2_2") (pintype "passive"))
      (node (ref "C16") (pin "2") (pinfunction "2_2") (pintype "passive"))
      (node (ref "C17") (pin "2") (pinfunction "2_2") (pintype "passive"))
      (node (ref "C18") (pin "2") (pinfunction "2_2") (pintype "passive"))
      (node (ref "C19") (pin "2") (pinfunction "2_2") (pintype "passive"))
      (node (ref "C2") (pin "2") (pinfunction "2_2") (pintype "passive"))
      (node (ref "C3") (pin "2") (pinfunction "2_2") (pintype "passive"))
      (node (ref "C4") (pin "2") (pinfunction "2_2") (pintype "passive"))
      (node (ref "F10") (pin "R1") (pinfunction "2_R1") (pintype "bidirectional"))
      (node (ref "F10") (pin "R2") (pinfunction "2_R2") (pintype "bidirectional"))
      (node (ref "R48") (pin "1") (pinfunction "1_1") (pintype "passive"))
      (node (ref "RB2") (pin "1") (pinfunction "1_1") (pintype "passive"))
      (node (ref "U$2") (pin "26") (pinfunction "C0_26") (pintype "bidirectional"))
      (node (ref "U$2") (pin "30") (pinfunction "V-**_30") (pintype "bidirectional"))
      (node (ref "U$2") (pin "31") (pinfunction "V-_31") (pintype "bidirectional"))
      (node (ref "U$2") (pin "43") (pinfunction "SDI(NC)_43") (pintype "bidirectional"))
      (node (ref "U$2") (pin "44") (pinfunction "SDO(NC)_44") (pintype "bidirectional"))
    )
    (net (code "45") (name "Net-(CONTACT1-S)") (class "Default")
      (node (ref "CONTACT1") (pin "P$1") (pinfunction "S_P$1") (pintype "passive"))
      (node (ref "F1") (pin "L1") (pinfunction "1_L1") (pintype "bidirectional"))
      (node (ref "F1") (pin "L2") (pinfunction "1_L2") (pintype "bidirectional"))
    )
    (net (code "46") (name "Net-(CONTACT2-S)") (class "Default")
      (node (ref "CONTACT2") (pin "P$1") (pinfunction "S_P$1") (pintype "passive"))
      (node (ref "F2") (pin "L1") (pinfunction "1_L1") (pintype "bidirectional"))
      (node (ref "F2") (pin "L2") (pinfunction "1_L2") (pintype "bidirectional"))
    )
    (net (code "47") (name "Net-(CONTACT3-S)") (class "Default")
      (node (ref "CONTACT3") (pin "P$1") (pinfunction "S_P$1") (pintype "passive"))
      (node (ref "F3") (pin "L1") (pinfunction "1_L1") (pintype "bidirectional"))
      (node (ref "F3") (pin "L2") (pinfunction "1_L2") (pintype "bidirectional"))
    )
    (net (code "48") (name "Net-(CONTACT4-S)") (class "Default")
      (node (ref "CONTACT4") (pin "P$1") (pinfunction "S_P$1") (pintype "passive"))
      (node (ref "F4") (pin "L1") (pinfunction "1_L1") (pintype "bidirectional"))
      (node (ref "F4") (pin "L2") (pinfunction "1_L2") (pintype "bidirectional"))
    )
    (net (code "49") (name "Net-(CONTACT5-S)") (class "Default")
      (node (ref "CONTACT5") (pin "P$1") (pinfunction "S_P$1") (pintype "passive"))
      (node (ref "F5") (pin "L1") (pinfunction "1_L1") (pintype "bidirectional"))
      (node (ref "F5") (pin "L2") (pinfunction "1_L2") (pintype "bidirectional"))
    )
    (net (code "50") (name "Net-(CONTACT6-S)") (class "Default")
      (node (ref "CONTACT6") (pin "P$1") (pinfunction "S_P$1") (pintype "passive"))
      (node (ref "F6") (pin "L1") (pinfunction "1_L1") (pintype "bidirectional"))
      (node (ref "F6") (pin "L2") (pinfunction "1_L2") (pintype "bidirectional"))
    )
    (net (code "51") (name "Net-(CONTACT7-S)") (class "Default")
      (node (ref "CONTACT7") (pin "P$1") (pinfunction "S_P$1") (pintype "passive"))
      (node (ref "F7") (pin "L1") (pinfunction "1_L1") (pintype "bidirectional"))
      (node (ref "F7") (pin "L2") (pinfunction "1_L2") (pintype "bidirectional"))
    )
    (net (code "52") (name "Net-(CONTACT8-S)") (class "Default")
      (node (ref "CONTACT8") (pin "P$1") (pinfunction "S_P$1") (pintype "passive"))
      (node (ref "F8") (pin "L1") (pinfunction "1_L1") (pintype "bidirectional"))
      (node (ref "F8") (pin "L2") (pinfunction "1_L2") (pintype "bidirectional"))
    )
    (net (code "53") (name "Net-(CONTACT9-S)") (class "Default")
      (node (ref "CONTACT9") (pin "P$1") (pinfunction "S_P$1") (pintype "passive"))
      (node (ref "F9") (pin "L1") (pinfunction "1_L1") (pintype "bidirectional"))
      (node (ref "F9") (pin "L2") (pinfunction "1_L2") (pintype "bidirectional"))
    )
    (net (code "54") (name "Net-(CONTACT10-S)") (class "Default")
      (node (ref "CONTACT10") (pin "P$1") (pinfunction "S_P$1") (pintype "passive"))
      (node (ref "F10") (pin "L1") (pinfunction "1_L1") (pintype "bidirectional"))
      (node (ref "F10") (pin "L2") (pinfunction "1_L2") (pintype "bidirectional"))
    )
    (net (code "55") (name "Net-(Q3-D)") (class "Default")
      (node (ref "Q3") (pin "3") (pinfunction "D_3") (pintype "passive"))
      (node (ref "R21") (pin "2") (pinfunction "2_2") (pintype "passive"))
    )
    (net (code "56") (name "Net-(Q3-G)") (class "Default")
      (node (ref "Q3") (pin "1") (pinfunction "G_1") (pintype "passive"))
      (node (ref "R20") (pin "1") (pinfunction "1_1") (pintype "passive"))
    )
    (net (code "57") (name "Net-(Q4-D)") (class "Default")
      (node (ref "Q4") (pin "3") (pinfunction "D_3") (pintype "passive"))
      (node (ref "R24") (pin "2") (pinfunction "2_2") (pintype "passive"))
    )
    (net (code "58") (name "Net-(Q4-G)") (class "Default")
      (node (ref "Q4") (pin "1") (pinfunction "G_1") (pintype "passive"))
      (node (ref "R23") (pin "1") (pinfunction "1_1") (pintype "passive"))
    )
    (net (code "59") (name "Net-(Q5-D)") (class "Default")
      (node (ref "Q5") (pin "3") (pinfunction "D_3") (pintype "passive"))
      (node (ref "R27") (pin "2") (pinfunction "2_2") (pintype "passive"))
    )
    (net (code "60") (name "Net-(Q5-G)") (class "Default")
      (node (ref "Q5") (pin "1") (pinfunction "G_1") (pintype "passive"))
      (node (ref "R26") (pin "1") (pinfunction "1_1") (pintype "passive"))
    )
    (net (code "61") (name "Net-(Q6-D)") (class "Default")
      (node (ref "Q6") (pin "3") (pinfunction "D_3") (pintype "passive"))
      (node (ref "R30") (pin "2") (pinfunction "2_2") (pintype "passive"))
    )
    (net (code "62") (name "Net-(Q6-G)") (class "Default")
      (node (ref "Q6") (pin "1") (pinfunction "G_1") (pintype "passive"))
      (node (ref "R29") (pin "1") (pinfunction "1_1") (pintype "passive"))
    )
    (net (code "63") (name "Net-(Q8-D)") (class "Default")
      (node (ref "Q8") (pin "3") (pinfunction "D_3") (pintype "passive"))
      (node (ref "R36") (pin "2") (pinfunction "2_2") (pintype "passive"))
    )
    (net (code "64") (name "Net-(Q8-G)") (class "Default")
      (node (ref "Q8") (pin "1") (pinfunction "G_1") (pintype "passive"))
      (node (ref "R35") (pin "1") (pinfunction "1_1") (pintype "passive"))
    )
    (net (code "65") (name "Net-(Q9-D)") (class "Default")
      (node (ref "Q9") (pin "3") (pinfunction "D_3") (pintype "passive"))
      (node (ref "R39") (pin "2") (pinfunction "2_2") (pintype "passive"))
    )
    (net (code "66") (name "Net-(Q9-G)") (class "Default")
      (node (ref "Q9") (pin "1") (pinfunction "G_1") (pintype "passive"))
      (node (ref "R38") (pin "1") (pinfunction "1_1") (pintype "passive"))
    )
    (net (code "67") (name "Net-(Q10-D)") (class "Default")
      (node (ref "Q10") (pin "3") (pinfunction "D_3") (pintype "passive"))
      (node (ref "R42") (pin "2") (pinfunction "2_2") (pintype "passive"))
    )
    (net (code "68") (name "Net-(Q10-G)") (class "Default")
      (node (ref "Q10") (pin "1") (pinfunction "G_1") (pintype "passive"))
      (node (ref "R41") (pin "1") (pinfunction "1_1") (pintype "passive"))
    )
    (net (code "69") (name "Net-(Q11-D)") (class "Default")
      (node (ref "Q11") (pin "3") (pinfunction "D_3") (pintype "passive"))
      (node (ref "R45") (pin "2") (pinfunction "2_2") (pintype "passive"))
    )
    (net (code "70") (name "Net-(Q11-G)") (class "Default")
      (node (ref "Q11") (pin "1") (pinfunction "G_1") (pintype "passive"))
      (node (ref "R44") (pin "1") (pinfunction "1_1") (pintype "passive"))
    )
    (net (code "71") (name "Net-(Q12-D)") (class "Default")
      (node (ref "Q12") (pin "3") (pinfunction "D_3") (pintype "passive"))
      (node (ref "R48") (pin "2") (pinfunction "2_2") (pintype "passive"))
    )
    (net (code "72") (name "Net-(Q12-G)") (class "Default")
      (node (ref "Q12") (pin "1") (pinfunction "G_1") (pintype "passive"))
      (node (ref "R47") (pin "1") (pinfunction "1_1") (pintype "passive"))
    )
    (net (code "73") (name "Net-(TRANSFORMER-A-CX)") (class "Default")
      (node (ref "C18") (pin "1") (pinfunction "1_1") (pintype "passive"))
      (node (ref "TRANSFORMER-") (pin "10") (pinfunction "CX_10") (pintype "passive"))
    )
    (net (code "74") (name "Net-(TRANSFORMER-A-X+)") (class "Default")
      (node (ref "R49") (pin "1") (pinfunction "1_1") (pintype "passive"))
      (node (ref "TRANSFORMER-") (pin "11") (pinfunction "X+_11") (pintype "passive"))
      (node (ref "U$2") (pin "42") (pinfunction "SCK(IPA)_42") (pintype "bidirectional"))
    )
    (net (code "75") (name "Net-(TRANSFORMER-A-X-)") (class "Default")
      (node (ref "R49") (pin "2") (pinfunction "2_2") (pintype "passive"))
      (node (ref "TRANSFORMER-") (pin "9") (pinfunction "X-_9") (pintype "passive"))
      (node (ref "U$2") (pin "41") (pinfunction "CSB(IMA)_41") (pintype "bidirectional"))
    )
    (net (code "76") (name "Net-(TRANSFORMER-B-CX)") (class "Default")
      (node (ref "C17") (pin "1") (pinfunction "1_1") (pintype "passive"))
      (node (ref "TRANSFORMER-") (pin "15") (pinfunction "CX_15") (pintype "passive"))
    )
    (net (code "77") (name "Net-(TRANSFORMER-B-X+)") (class "Default")
      (node (ref "R1") (pin "1") (pinfunction "1_1") (pintype "passive"))
      (node (ref "TRANSFORMER-") (pin "16") (pinfunction "X+_16") (pintype "passive"))
      (node (ref "U$2") (pin "48") (pinfunction "IPB_48") (pintype "bidirectional"))
    )
    (net (code "78") (name "Net-(TRANSFORMER-B-X-)") (class "Default")
      (node (ref "R1") (pin "2") (pinfunction "2_2") (pintype "passive"))
      (node (ref "TRANSFORMER-") (pin "14") (pinfunction "X-_14") (pintype "passive"))
      (node (ref "U$2") (pin "47") (pinfunction "IMB_47") (pintype "bidirectional"))
    )
    (net (code "79") (name "Net-(U$2-IBIAS)") (class "Default")
      (node (ref "RB1") (pin "2") (pinfunction "2_2") (pintype "passive"))
      (node (ref "U$2") (pin "45") (pinfunction "IBIAS_45") (pintype "bidirectional"))
    )
    (net (code "80") (name "Net-(U$2-ICMP)") (class "Default")
      (node (ref "RB1") (pin "1") (pinfunction "1_1") (pintype "passive"))
      (node (ref "RB2") (pin "2") (pinfunction "2_2") (pintype "passive"))
      (node (ref "U$2") (pin "46") (pinfunction "ICMP_46") (pintype "bidirectional"))
    )
    (net (code "81") (name "unconnected-(TRANSFORMER-A-CD-Pad7)") (class "Default")
      (node (ref "TRANSFORMER-") (pin "7") (pinfunction "CD_7") (pintype "passive"))
    )
    (net (code "82") (name "unconnected-(TRANSFORMER-B-CD-Pad2)") (class "Default")
      (node (ref "TRANSFORMER-") (pin "2") (pinfunction "CD_2") (pintype "passive"))
    )
    (net (code "83") (name "unconnected-(U$2-GPI05-Pad33)") (class "Default")
      (node (ref "U$2") (pin "33") (pinfunction "GPI05_33") (pintype "bidirectional"))
    )
    (net (code "84") (name "unconnected-(U$2-S6-Pad15)") (class "Default")
      (node (ref "U$2") (pin "15") (pinfunction "S6_15") (pintype "bidirectional"))
    )
    (net (code "85") (name "unconnected-(U$2-S11-Pad5)") (class "Default")
      (node (ref "U$2") (pin "5") (pinfunction "S11_5") (pintype "bidirectional"))
    )
    (net (code "86") (name "unconnected-(U$2-S12-Pad3)") (class "Default")
      (node (ref "U$2") (pin "3") (pinfunction "S12_3") (pintype "bidirectional"))
    )
    (net (code "87") (name "unconnected-(U$2-WDT-Pad39)") (class "Default")
      (node (ref "U$2") (pin "39") (pinfunction "WDT_39") (pintype "bidirectional"))
    )
  )
)
